# RS14-BatLockPCB.net
KiCad netlist of a schematic drawn in EAGLE
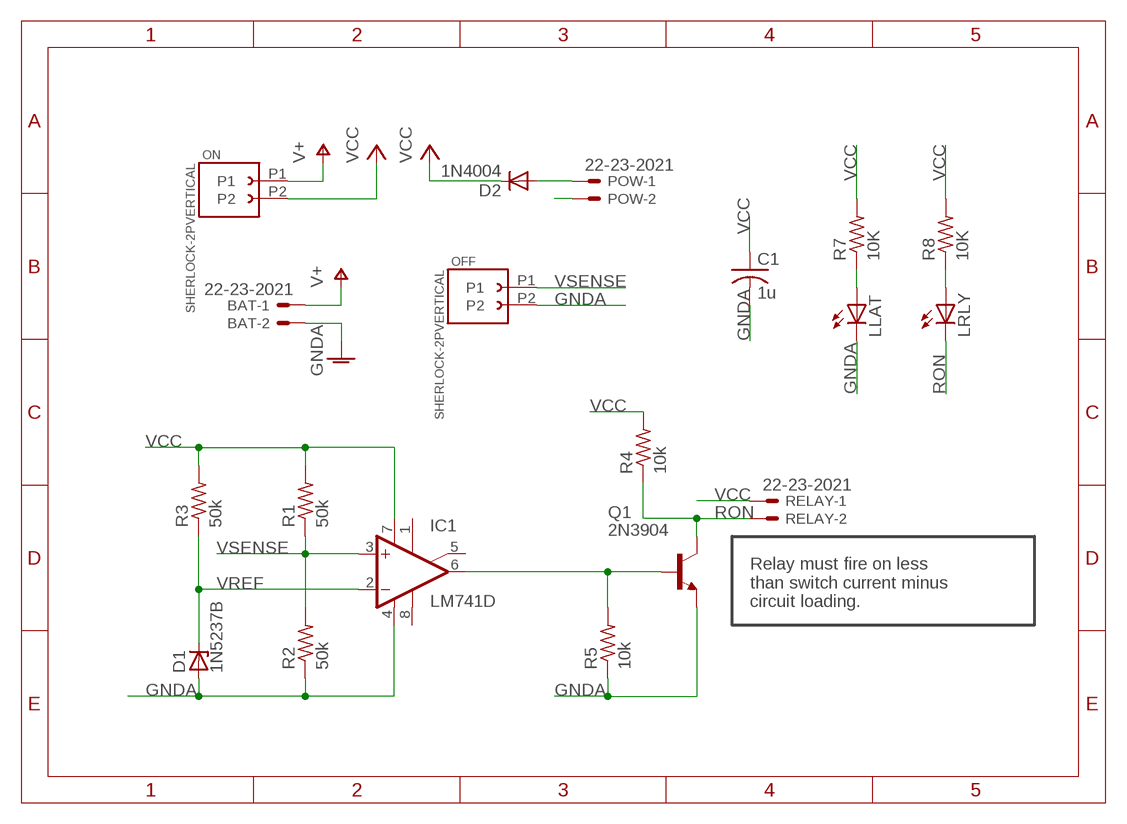
[diagram p0: schematic, sheet 1]

(export (version "E")
  (design (tool "Eeschema 10.0.6"))
  (components
    (comp (ref "BAT")
      (value "22-23-2021")
      (footprint "eagle-import:22-23-2021")
      (fields (field (name "MF") "MOLEX"))
      (libsource (lib "eagle-import") (part "22-23-2021"))
    )
    (comp (ref "C1")
      (value "1u")
      (footprint "eagle-import:C025-025X050")
      (libsource (lib "eagle-import") (part "C-US025-025X050"))
    )
    (comp (ref "D1")
      (value "1N5237B")
      (footprint "eagle-import:DO35Z10")
      (libsource (lib "eagle-import") (part "1N821"))
    )
    (comp (ref "D2")
      (value "1N4004")
      (footprint "eagle-import:DO41-10")
      (libsource (lib "eagle-import") (part "1N4004"))
    )
    (comp (ref "IC1")
      (value "LM741D")
      (footprint "eagle-import:SO08")
      (libsource (lib "eagle-import") (part "741DLM"))
    )
    (comp (ref "LLAT")
      (value "LED3MM")
      (footprint "eagle-import:LED3MM")
      (libsource (lib "eagle-import") (part "LED3MM"))
    )
    (comp (ref "LRLY")
      (value "LED3MM")
      (footprint "eagle-import:LED3MM")
      (libsource (lib "eagle-import") (part "LED3MM"))
    )
    (comp (ref "OFF")
      (value "SHERLOCK-2PVERTICAL")
      (footprint "eagle-import:35362-02__")
      (libsource (lib "eagle-import") (part "SHERLOCK-2PVERTICAL"))
    )
    (comp (ref "ON")
      (value "SHERLOCK-2PVERTICAL")
      (footprint "eagle-import:35362-02__")
      (libsource (lib "eagle-import") (part "SHERLOCK-2PVERTICAL"))
    )
    (comp (ref "POW")
      (value "22-23-2021")
      (footprint "eagle-import:22-23-2021")
      (fields (field (name "MF") "MOLEX"))
      (libsource (lib "eagle-import") (part "22-23-2021"))
    )
    (comp (ref "Q1")
      (value "2N3904")
      (footprint "eagle-import:TO92")
      (libsource (lib "eagle-import") (part "2N3904"))
    )
    (comp (ref "R1")
      (value "50k")
      (footprint "eagle-import:0204_7")
      (libsource (lib "eagle-import") (part "R-US_0204/7"))
    )
    (comp (ref "R2")
      (value "50k")
      (footprint "eagle-import:0204_7")
      (libsource (lib "eagle-import") (part "R-US_0204/7"))
    )
    (comp (ref "R3")
      (value "50k")
      (footprint "eagle-import:0204_7")
      (libsource (lib "eagle-import") (part "R-US_0204/7"))
    )
    (comp (ref "R4")
      (value "10k")
      (footprint "eagle-import:0204_7")
      (libsource (lib "eagle-import") (part "R-US_0204/7"))
    )
    (comp (ref "R5")
      (value "10k")
      (footprint "eagle-import:0204_7")
      (libsource (lib "eagle-import") (part "R-US_0204/7"))
    )
    (comp (ref "R7")
      (value "10K")
      (footprint "eagle-import:0204_7")
      (libsource (lib "eagle-import") (part "R-US_0204/7"))
    )
    (comp (ref "R8")
      (value "10K")
      (footprint "eagle-import:0204_7")
      (libsource (lib "eagle-import") (part "R-US_0204/7"))
    )
    (comp (ref "RELAY")
      (value "22-23-2021")
      (footprint "eagle-import:22-23-2021")
      (fields (field (name "MF") "MOLEX"))
      (libsource (lib "eagle-import") (part "22-23-2021"))
    )
  )
  (nets
    (net (code "1") (name "/RON") (class "Default")
      (node (ref "LRLY") (pin "K") (pinfunction "C_K") (pintype "passive"))
      (node (ref "Q1") (pin "1") (pinfunction "C_1") (pintype "passive"))
      (node (ref "R4") (pin "1") (pinfunction "1_1") (pintype "passive"))
      (node (ref "RELAY") (pin "2") (pinfunction "S_2") (pintype "passive"))
    )
    (net (code "2") (name "/VREF") (class "Default")
      (node (ref "D1") (pin "C") (pinfunction "C_C") (pintype "passive"))
      (node (ref "IC1") (pin "2") (pinfunction "-IN_2") (pintype "input"))
      (node (ref "R3") (pin "1") (pinfunction "1_1") (pintype "passive"))
    )
    (net (code "3") (name "/VSENSE") (class "Default")
      (node (ref "IC1") (pin "3") (pinfunction "+IN_3") (pintype "input"))
      (node (ref "OFF") (pin "P1") (pinfunction "P1_P1") (pintype "bidirectional"))
      (node (ref "R1") (pin "1") (pinfunction "1_1") (pintype "passive"))
      (node (ref "R2") (pin "2") (pinfunction "2_2") (pintype "passive"))
    )
    (net (code "4") (name "GNDA") (class "Default")
      (node (ref "BAT") (pin "2") (pinfunction "S_2") (pintype "passive"))
      (node (ref "C1") (pin "2") (pinfunction "2_2") (pintype "passive"))
      (node (ref "D1") (pin "A") (pinfunction "A_A") (pintype "passive"))
      (node (ref "IC1") (pin "4") (pinfunction "V-_4") (pintype "power_in"))
      (node (ref "LLAT") (pin "K") (pinfunction "C_K") (pintype "passive"))
      (node (ref "OFF") (pin "P2") (pinfunction "P2_P2") (pintype "bidirectional"))
      (node (ref "Q1") (pin "3") (pinfunction "E_3") (pintype "passive"))
      (node (ref "R2") (pin "1") (pinfunction "1_1") (pintype "passive"))
      (node (ref "R5") (pin "1") (pinfunction "1_1") (pintype "passive"))
    )
    (net (code "5") (name "Net-(IC1-OUT)") (class "Default")
      (node (ref "IC1") (pin "6") (pinfunction "OUT_6") (pintype "output"))
      (node (ref "Q1") (pin "2") (pinfunction "B_2") (pintype "passive"))
      (node (ref "R5") (pin "2") (pinfunction "2_2") (pintype "passive"))
    )
    (net (code "6") (name "Net-(LLAT-PadA)") (class "Default")
      (node (ref "LLAT") (pin "A") (pinfunction "A_A") (pintype "passive"))
      (node (ref "R7") (pin "1") (pinfunction "1_1") (pintype "passive"))
    )
    (net (code "7") (name "Net-(LRLY-PadA)") (class "Default")
      (node (ref "LRLY") (pin "A") (pinfunction "A_A") (pintype "passive"))
      (node (ref "R8") (pin "1") (pinfunction "1_1") (pintype "passive"))
    )
    (net (code "8") (name "Net-(POWA-S)") (class "Default")
      (node (ref "D2") (pin "A") (pinfunction "A_A") (pintype "passive"))
      (node (ref "POW") (pin "1") (pinfunction "S_1") (pintype "passive"))
    )
    (net (code "9") (name "V+") (class "Default")
      (node (ref "BAT") (pin "1") (pinfunction "S_1") (pintype "passive"))
      (node (ref "ON") (pin "P1") (pinfunction "P1_P1") (pintype "bidirectional"))
    )
    (net (code "10") (name "VCC") (class "Default")
      (node (ref "C1") (pin "1") (pinfunction "1_1") (pintype "passive"))
      (node (ref "D2") (pin "C") (pinfunction "C_C") (pintype "passive"))
      (node (ref "IC1") (pin "7") (pinfunction "V+_7") (pintype "power_in"))
      (node (ref "ON") (pin "P2") (pinfunction "P2_P2") (pintype "bidirectional"))
      (node (ref "R1") (pin "2") (pinfunction "2_2") (pintype "passive"))
      (node (ref "R3") (pin "2") (pinfunction "2_2") (pintype "passive"))
      (node (ref "R4") (pin "2") (pinfunction "2_2") (pintype "passive"))
      (node (ref "R7") (pin "2") (pinfunction "2_2") (pintype "passive"))
      (node (ref "R8") (pin "2") (pinfunction "2_2") (pintype "passive"))
      (node (ref "RELAY") (pin "1") (pinfunction "S_1") (pintype "passive"))
    )
    (net (code "11") (name "unconnected-(IC1-ON1-Pad1)") (class "Default")
      (node (ref "IC1") (pin "1") (pinfunction "ON1_1") (pintype "passive"))
    )
    (net (code "12") (name "unconnected-(IC1-ON2-Pad5)") (class "Default")
      (node (ref "IC1") (pin "5") (pinfunction "ON2_5") (pintype "passive"))
    )
    (net (code "13") (name "unconnected-(IC1-OPT-Pad8)") (class "Default")
      (node (ref "IC1") (pin "8") (pinfunction "OPT_8") (pintype "passive"))
    )
    (net (code "14") (name "unconnected-(POWB-S-Pad2)") (class "Default")
      (node (ref "POW") (pin "2") (pinfunction "S_2") (pintype "passive"))
    )
  )
)
